# u-cont.net
KiCad netlist of a schematic drawn in Altium Designer
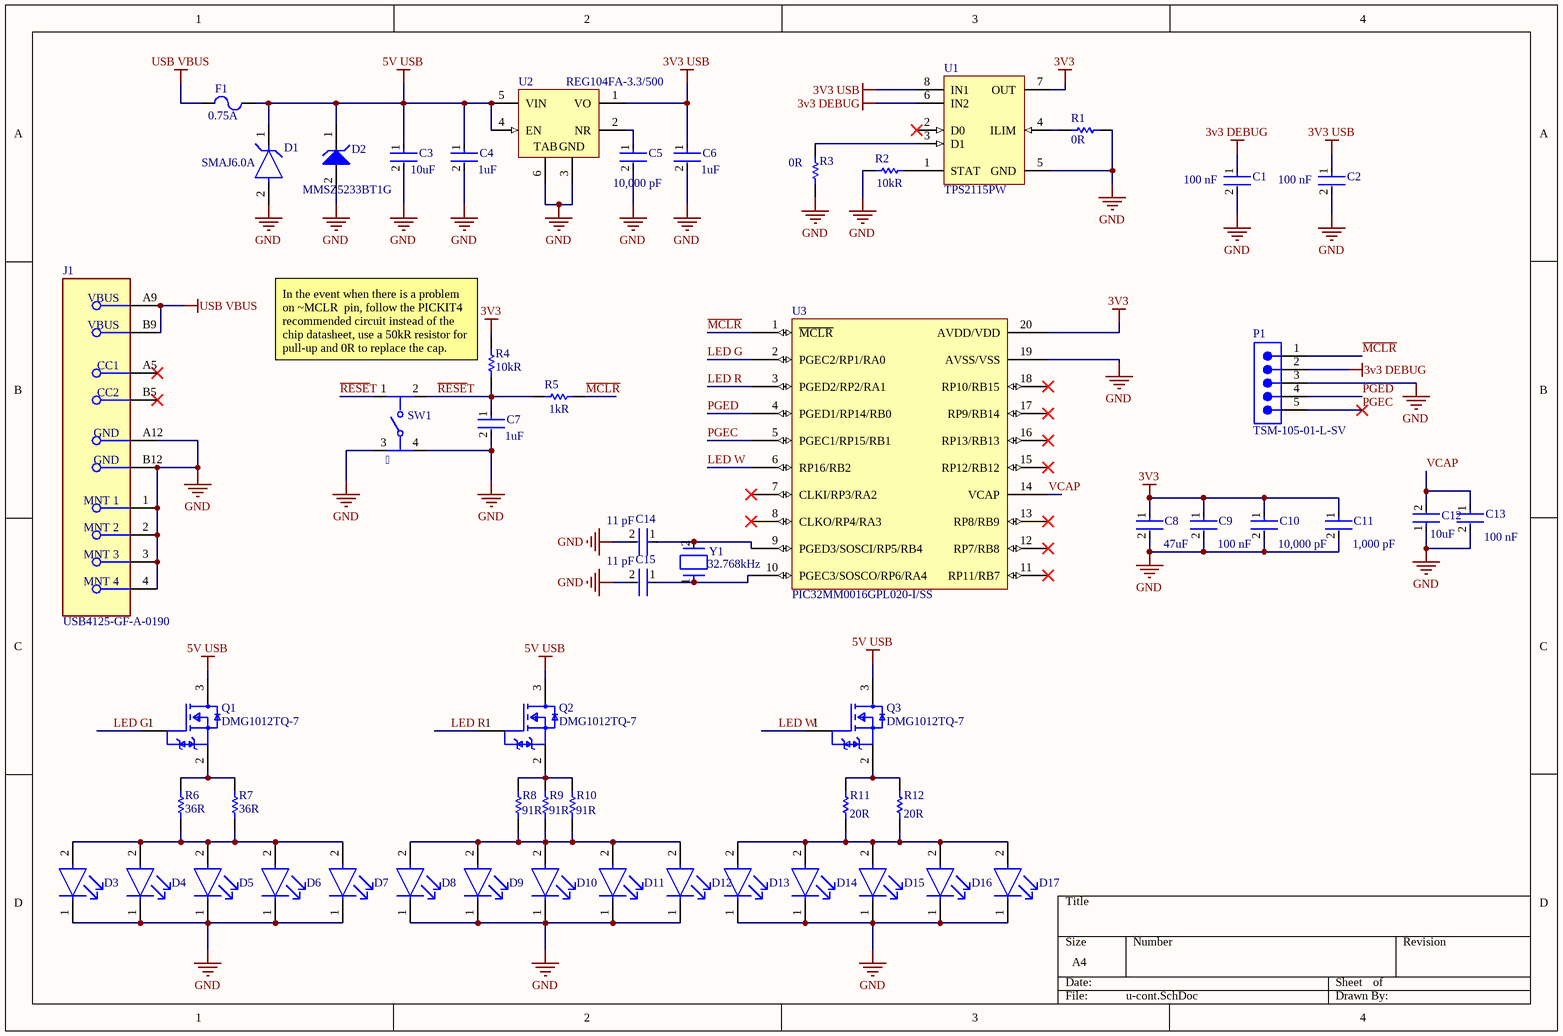
[diagram p0: u-cont.SchDoc]

(export (version "E")
  (design (tool "Eeschema 10.0.6"))
  (components
    (comp (ref "C1")
      (value "CC0805KRX7R8BB104")
      (footprint "FP-CC0805-0_85-MFG")
      (description "CAP CER 0.1UF 25V X7R 0805")
      (fields
        (field (name "TOLERANCE") "0.1")
        (field (name "MANUFACTURER") "Yageo")
        (field (name "CAPACITANCE") "100 nF")
      )
      (libsource (lib "Altium Content Vault") (part "11868f565c42a9108669ba33697ecf6"))
    )
    (comp (ref "C2")
      (value "CC0805KRX7R8BB104")
      (footprint "FP-CC0805-0_85-MFG")
      (description "CAP CER 0.1UF 25V X7R 0805")
      (fields
        (field (name "TOLERANCE") "0.1")
        (field (name "MANUFACTURER") "Yageo")
        (field (name "CAPACITANCE") "100 nF")
      )
      (libsource (lib "Altium Content Vault") (part "11868f565c42a9108669ba33697ecf6"))
    )
    (comp (ref "C3")
      (value "GRM21BR61E106KA73L")
      (footprint "FP-GRM21B-0_15-IPC_C")
      (description "Chip Multilayer Ceramic Capacitors for General Purpose, 0805, 10uF, X5R, 15%, 10%, 25V")
      (fields
        (field (name "VOLTAGE") "25V")
        (field (name "CAPACITANCE") "10uF")
        (field (name "TOLERANCE") "10%")
      )
      (libsource (lib "Altium Content Vault") (part "b4654b650e69147ec39a6b967a45e02"))
    )
    (comp (ref "C4")
      (value "C2012X5R1E105K125AA")
      (footprint "FP-C2012-125-0_2-IPC_A")
      (description "Multilayer Ceramic Capacitors 1μF ±10% 25V X5R SMD 0805")
      (fields
        (field (name "VOLTAGE") "25V")
        (field (name "CAPACITANCE") "1uF")
        (field (name "TOLERANCE") "10%")
      )
      (libsource (lib "Altium Content Vault") (part "b4654b650e69147ec39a6b967a45e02"))
    )
    (comp (ref "C5")
      (value "C0805C103J5RACTU")
      (footprint "FP-C0805C-DN-MFG")
      (description "CAP CER 10000PF 50V X7R 0805")
      (fields
        (field (name "MANUFACTURER") "KEMET")
        (field (name "CAPACITANCE") "10,000 pF")
        (field (name "OCTOPART") "https://octopart.com/c0805c103j5ractu-kemet-133473")
      )
      (libsource (lib "Altium Content Vault") (part "b4654b650e69147ec39a6b967a45e02"))
    )
    (comp (ref "C6")
      (value "C2012X5R1E105K125AA")
      (footprint "FP-C2012-125-0_2-IPC_A")
      (description "Multilayer Ceramic Capacitors 1μF ±10% 25V X5R SMD 0805")
      (fields
        (field (name "VOLTAGE") "25V")
        (field (name "CAPACITANCE") "1uF")
        (field (name "TOLERANCE") "10%")
      )
      (libsource (lib "Altium Content Vault") (part "b4654b650e69147ec39a6b967a45e02"))
    )
    (comp (ref "C7")
      (value "C2012X5R1E105K125AA")
      (footprint "FP-C2012-125-0_2-IPC_A")
      (description "Multilayer Ceramic Capacitors 1μF ±10% 25V X5R SMD 0805")
      (fields
        (field (name "VOLTAGE") "25V")
        (field (name "CAPACITANCE") "1uF")
        (field (name "TOLERANCE") "10%")
      )
      (libsource (lib "Altium Content Vault") (part "b4654b650e69147ec39a6b967a45e02"))
    )
    (comp (ref "C8")
      (value "C0805C476M9PACTU")
      (footprint "FP-C0805C476M9PACTU-MFG")
      (description "CAP CER 47UF 6.3V X5R 0805")
      (fields
        (field (name "VOLTAGE") "6.3V")
        (field (name "TOLERANCE") "20%")
        (field (name "CAPACITANCE") "47uF")
      )
      (libsource (lib "Altium Content Vault") (part "11868f565c42a9108669ba33697ecf6"))
    )
    (comp (ref "C9")
      (value "CC0805KRX7R8BB104")
      (footprint "FP-CC0805-0_85-MFG")
      (description "CAP CER 0.1UF 25V X7R 0805")
      (fields
        (field (name "TOLERANCE") "0.1")
        (field (name "MANUFACTURER") "Yageo")
        (field (name "CAPACITANCE") "100 nF")
      )
      (libsource (lib "Altium Content Vault") (part "11868f565c42a9108669ba33697ecf6"))
    )
    (comp (ref "C10")
      (value "C0805C103J5RACTU")
      (footprint "FP-C0805C-DN-MFG")
      (description "CAP CER 10000PF 50V X7R 0805")
      (fields
        (field (name "MANUFACTURER") "KEMET")
        (field (name "CAPACITANCE") "10,000 pF")
        (field (name "OCTOPART") "https://octopart.com/c0805c103j5ractu-kemet-133473")
      )
      (libsource (lib "Altium Content Vault") (part "b4654b650e69147ec39a6b967a45e02"))
    )
    (comp (ref "C11")
      (value "C0805C102K5RACTU")
      (footprint "FP-C0805C-DN-MFG")
      (description "CAP CER 1000PF 50V X7R 0805")
      (fields
        (field (name "CAPACITANCE") "1,000 pF")
        (field (name "OCTOPART") "https://octopart.com/c0805c102k5ractu-kemet-93010")
        (field (name "TOLERANCE") "0.1")
      )
      (libsource (lib "Altium Content Vault") (part "b4654b650e69147ec39a6b967a45e02"))
    )
    (comp (ref "C12")
      (value "C0805C106K8PACTU")
      (footprint "FP-C0805C-DG-MFG")
      (description "CAP CER 10UF 10V X5R 0805")
      (fields
        (field (name "TOLERANCE") "10%")
        (field (name "MANUFACTURER") "Kemet")
        (field (name "CAPACITANCE") "10uF")
      )
      (libsource (lib "Altium Content Vault") (part "11868f565c42a9108669ba33697ecf6"))
    )
    (comp (ref "C13")
      (value "CC0805KRX7R8BB104")
      (footprint "FP-CC0805-0_85-MFG")
      (description "CAP CER 0.1UF 25V X7R 0805")
      (fields
        (field (name "TOLERANCE") "0.1")
        (field (name "MANUFACTURER") "Yageo")
        (field (name "CAPACITANCE") "100 nF")
      )
      (libsource (lib "Altium Content Vault") (part "11868f565c42a9108669ba33697ecf6"))
    )
    (comp (ref "C14")
      (value "11 pF")
      (footprint "FP-C0805C-DN-MFG")
      (description "CAP CER 11PF 50V 5% NP0 0805")
      (fields (field (name "TOLERANCE") "0.05") (field (name "MANUFACTURER PART NUMBER") "C0805C110J5GACTU"))
      (libsource (lib "Altium Content Vault") (part "b4654b650e69147ec39a6b967a45e02"))
    )
    (comp (ref "C15")
      (value "11 pF")
      (footprint "FP-C0805C-DN-MFG")
      (description "CAP CER 11PF 50V 5% NP0 0805")
      (fields (field (name "TOLERANCE") "0.05") (field (name "MANUFACTURER PART NUMBER") "C0805C110J5GACTU"))
      (libsource (lib "Altium Content Vault") (part "b4654b650e69147ec39a6b967a45e02"))
    )
    (comp (ref "D1")
      (value "SMAJ6.0A")
      (footprint "FP-SMAJ-MFG")
      (description "TVS DIODE 6V 10.3V DO214AC")
      (fields
        (field (name "OCTOPART") "https://octopart.com/smaj6.0a-littelfuse-350212")
        (field (name "MANUFACTURER") "Littelfuse")
      )
      (libsource (lib "Altium Content Vault") (part "f813f71cba58e380607f5dd3caf9714"))
    )
    (comp (ref "D2")
      (value "MMSZ5233BT1G")
      (footprint "ONSC-SOD-123-2-425-04_V")
      (description "Zener Voltage Regulator, 500 mW, 2-Pin SOD-123, Pb-Free, Tape and Reel")
      (fields (field (name "MANUFACTURER") "On Semiconductor"))
      (libsource (lib "Altium Content Vault") (part "ONSC-K1A2-2"))
    )
    (comp (ref "D3")
      (value "150060GS75000")
      (footprint "FP-150060GS75000-MFG")
      (description "Led, Green, 520 Nm, 3.2 V, 30 Ma, 430 Mcd Rohs Compliant: Yes")
      (libsource (lib "Open Robotics Drivetrain ELEC") (part "8706943c75ba83719d021d2fdc84c58"))
    )
    (comp (ref "D4")
      (value "150060GS75000")
      (footprint "FP-150060GS75000-MFG")
      (description "Led, Green, 520 Nm, 3.2 V, 30 Ma, 430 Mcd Rohs Compliant: Yes")
      (libsource (lib "Open Robotics Drivetrain ELEC") (part "8706943c75ba83719d021d2fdc84c58"))
    )
    (comp (ref "D5")
      (value "150060GS75000")
      (footprint "FP-150060GS75000-MFG")
      (description "Led, Green, 520 Nm, 3.2 V, 30 Ma, 430 Mcd Rohs Compliant: Yes")
      (libsource (lib "Open Robotics Drivetrain ELEC") (part "8706943c75ba83719d021d2fdc84c58"))
    )
    (comp (ref "D6")
      (value "150060GS75000")
      (footprint "FP-150060GS75000-MFG")
      (description "Led, Green, 520 Nm, 3.2 V, 30 Ma, 430 Mcd Rohs Compliant: Yes")
      (libsource (lib "Open Robotics Drivetrain ELEC") (part "8706943c75ba83719d021d2fdc84c58"))
    )
    (comp (ref "D7")
      (value "150060GS75000")
      (footprint "FP-150060GS75000-MFG")
      (description "Led, Green, 520 Nm, 3.2 V, 30 Ma, 430 Mcd Rohs Compliant: Yes")
      (libsource (lib "Open Robotics Drivetrain ELEC") (part "8706943c75ba83719d021d2fdc84c58"))
    )
    (comp (ref "D8")
      (value "150060GS75000")
      (footprint "FP-150060GS75000-MFG")
      (description "Led, Green, 520 Nm, 3.2 V, 30 Ma, 430 Mcd Rohs Compliant: Yes")
      (libsource (lib "Open Robotics Drivetrain ELEC") (part "8706943c75ba83719d021d2fdc84c58"))
    )
    (comp (ref "D9")
      (value "150060GS75000")
      (footprint "FP-150060GS75000-MFG")
      (description "Led, Green, 520 Nm, 3.2 V, 30 Ma, 430 Mcd Rohs Compliant: Yes")
      (libsource (lib "Open Robotics Drivetrain ELEC") (part "8706943c75ba83719d021d2fdc84c58"))
    )
    (comp (ref "D10")
      (value "150060GS75000")
      (footprint "FP-150060GS75000-MFG")
      (description "Led, Green, 520 Nm, 3.2 V, 30 Ma, 430 Mcd Rohs Compliant: Yes")
      (libsource (lib "Open Robotics Drivetrain ELEC") (part "8706943c75ba83719d021d2fdc84c58"))
    )
    (comp (ref "D11")
      (value "150060GS75000")
      (footprint "FP-150060GS75000-MFG")
      (description "Led, Green, 520 Nm, 3.2 V, 30 Ma, 430 Mcd Rohs Compliant: Yes")
      (libsource (lib "Open Robotics Drivetrain ELEC") (part "8706943c75ba83719d021d2fdc84c58"))
    )
    (comp (ref "D12")
      (value "150060GS75000")
      (footprint "FP-150060GS75000-MFG")
      (description "Led, Green, 520 Nm, 3.2 V, 30 Ma, 430 Mcd Rohs Compliant: Yes")
      (libsource (lib "Open Robotics Drivetrain ELEC") (part "8706943c75ba83719d021d2fdc84c58"))
    )
    (comp (ref "D13")
      (value "150060GS75000")
      (footprint "FP-150060GS75000-MFG")
      (description "Led, Green, 520 Nm, 3.2 V, 30 Ma, 430 Mcd Rohs Compliant: Yes")
      (libsource (lib "Open Robotics Drivetrain ELEC") (part "8706943c75ba83719d021d2fdc84c58"))
    )
    (comp (ref "D14")
      (value "150060GS75000")
      (footprint "FP-150060GS75000-MFG")
      (description "Led, Green, 520 Nm, 3.2 V, 30 Ma, 430 Mcd Rohs Compliant: Yes")
      (libsource (lib "Open Robotics Drivetrain ELEC") (part "8706943c75ba83719d021d2fdc84c58"))
    )
    (comp (ref "D15")
      (value "150060GS75000")
      (footprint "FP-150060GS75000-MFG")
      (description "Led, Green, 520 Nm, 3.2 V, 30 Ma, 430 Mcd Rohs Compliant: Yes")
      (libsource (lib "Open Robotics Drivetrain ELEC") (part "8706943c75ba83719d021d2fdc84c58"))
    )
    (comp (ref "D16")
      (value "150060GS75000")
      (footprint "FP-150060GS75000-MFG")
      (description "Led, Green, 520 Nm, 3.2 V, 30 Ma, 430 Mcd Rohs Compliant: Yes")
      (libsource (lib "Open Robotics Drivetrain ELEC") (part "8706943c75ba83719d021d2fdc84c58"))
    )
    (comp (ref "D17")
      (value "150060GS75000")
      (footprint "FP-150060GS75000-MFG")
      (description "Led, Green, 520 Nm, 3.2 V, 30 Ma, 430 Mcd Rohs Compliant: Yes")
      (libsource (lib "Open Robotics Drivetrain ELEC") (part "8706943c75ba83719d021d2fdc84c58"))
    )
    (comp (ref "F1")
      (value "1812L075/24DR")
      (footprint "LFUS-1812L07524DR_V")
      (description "Poly-Fuse(R) Resettable PTC, 24 V, 100 A, -40 to 85 degC, 2-Pin SMD, RoHS, Tape and Reel")
      (fields (field (name "MANUFACTURER") "Littelfuse") (field (name "HOLD CURRENT") "0.75A"))
      (libsource (lib "Altium Content Vault") (part "FUSE-2"))
    )
    (comp (ref "J1")
      (value "USB4125-GF-A-0190")
      (footprint "FP-USB4125-GF-A-0190-MFG")
      (description "CONN RCPT TYPE C 6P SMD RA")
      (libsource (lib "Altium Content Vault") (part "a055484d46e58b234844902c9fd883a"))
    )
    (comp (ref "P1")
      (value "TSM-105-01-L-SV")
      (footprint "SMTC-TSM-105-01-X-SV")
      (description "0.025\" SQ Post Header, Surface Mount, Vertical, -55 to 125 degC, 2.54 mm Pitch, 5-Pin, Male, RoHS")
      (fields (field (name "MANUFACTURER") "Samtec"))
      (libsource (lib "Altium Content Vault") (part "SMTC-TSM-105-01-X-SV"))
    )
    (comp (ref "Q1")
      (value "DMG1012TQ-7")
      (footprint "FP-SOT523-MFG")
      (description "MOSFET NCH 20V 630MA SOT523")
      (fields
        (field (name "OCTOPART") "https://octopart.com/dmg1012tq-7-diodes+inc.-74468997")
        (field (name "MANUFACTURER") "Diodes Inc.")
      )
      (libsource (lib "Altium Content Vault") (part "46b141b2f085c93750ed035ed02516a"))
    )
    (comp (ref "Q2")
      (value "DMG1012TQ-7")
      (footprint "FP-SOT523-MFG")
      (description "MOSFET NCH 20V 630MA SOT523")
      (fields
        (field (name "OCTOPART") "https://octopart.com/dmg1012tq-7-diodes+inc.-74468997")
        (field (name "MANUFACTURER") "Diodes Inc.")
      )
      (libsource (lib "Altium Content Vault") (part "46b141b2f085c93750ed035ed02516a"))
    )
    (comp (ref "Q3")
      (value "DMG1012TQ-7")
      (footprint "FP-SOT523-MFG")
      (description "MOSFET NCH 20V 630MA SOT523")
      (fields
        (field (name "OCTOPART") "https://octopart.com/dmg1012tq-7-diodes+inc.-74468997")
        (field (name "MANUFACTURER") "Diodes Inc.")
      )
      (libsource (lib "Altium Content Vault") (part "46b141b2f085c93750ed035ed02516a"))
    )
    (comp (ref "R1")
      (value "RC0805JR-070RL")
      (footprint "RESC2013X60X35ML10T20")
      (fields
        (field (name "RESISTANCE") "0R")
        (field (name "TOLERANCE") "5%")
        (field (name "MANUFACTURER") "Yageo")
      )
      (libsource (lib "Altium Content Vault") (part "RES-2"))
    )
    (comp (ref "R2")
      (value "RC0805FR-0710KL")
      (footprint "RESC2013X60X35NL10T20")
      (description "Chip Resistor, 10 KOhm, +/- 1%, 0.125 W, -55 to 155 degC, 0805 (2012 Metric), RoHS, Tape and Reel")
      (fields (field (name "MANUFACTURER") "Yageo") (field (name "RESISTANCE") "10kR"))
      (libsource (lib "Altium Content Vault") (part "RES-2"))
    )
    (comp (ref "R3")
      (value "RC0805JR-070RL")
      (footprint "RESC2013X60X35ML10T20")
      (fields
        (field (name "RESISTANCE") "0R")
        (field (name "TOLERANCE") "5%")
        (field (name "MANUFACTURER") "Yageo")
      )
      (libsource (lib "Altium Content Vault") (part "RES-2"))
    )
    (comp (ref "R4")
      (value "10kR")
      (footprint "RESC2013X60X35NL10T20")
      (description "Chip Resistor, 10 KOhm, +/- 1%, 0.125 W, -55 to 155 degC, 0805 (2012 Metric), RoHS, Tape and Reel")
      (fields (field (name "MANUFACTURER") "Yageo") (field (name "Comment") "RC0805FR-0710KL"))
      (libsource (lib "Altium Content Vault") (part "RES-2"))
    )
    (comp (ref "R5")
      (value "RC0805FR-071KL")
      (footprint "RESC2013X60X35ML10T20")
      (description "Chip Resistor, 1 KOhm, +/- 1%, 125 mW, -55 to 155 degC, 0805 (2012 Metric), RoHS, Tape and Reel")
      (fields
        (field (name "RESISTANCE") "1kR")
        (field (name "TOLERANCE") "1%")
        (field (name "MANUFACTURER") "Yageo")
      )
      (libsource (lib "Altium Content Vault") (part "RES-2"))
    )
    (comp (ref "R6")
      (value "36R")
      (footprint "RESC0805(2012)_L")
      (description "36R 0.125W 1% 0805 (2012 Metric)  SMD")
      (fields (field (name "POWER") "0.125 W") (field (name "TOLERANCE") "1 %"))
      (libsource (lib "Altium Content Vault") (part "RES"))
    )
    (comp (ref "R7")
      (value "36R")
      (footprint "RESC0805(2012)_L")
      (description "36R 0.125W 1% 0805 (2012 Metric)  SMD")
      (fields (field (name "POWER") "0.125 W") (field (name "TOLERANCE") "1 %"))
      (libsource (lib "Altium Content Vault") (part "RES"))
    )
    (comp (ref "R8")
      (value "ERJ-6GEYJ910V")
      (footprint "RESC2013X70X40NL20T20")
      (fields (field (name "MANUFACTURER") "Panasonic") (field (name "PARAMETER 1") "91R"))
      (libsource (lib "Altium Content Vault") (part "RES"))
    )
    (comp (ref "R9")
      (value "ERJ-6GEYJ910V")
      (footprint "RESC2013X70X40NL20T20")
      (fields (field (name "MANUFACTURER") "Panasonic") (field (name "PARAMETER 1") "91R"))
      (libsource (lib "Altium Content Vault") (part "RES"))
    )
    (comp (ref "R10")
      (value "ERJ-6GEYJ910V")
      (footprint "RESC2013X70X40NL20T20")
      (fields (field (name "MANUFACTURER") "Panasonic") (field (name "PARAMETER 1") "91R"))
      (libsource (lib "Altium Content Vault") (part "RES"))
    )
    (comp (ref "R11")
      (value "ERJ-6ENF20R0V")
      (footprint "RESC2013X70X40ML20T20")
      (fields (field (name "MANUFACTURER") "Panasonic") (field (name "PARAMETER 1") "20R"))
      (libsource (lib "Altium Content Vault") (part "RES"))
    )
    (comp (ref "R12")
      (value "ERJ-6ENF20R0V")
      (footprint "RESC2013X70X40ML20T20")
      (fields (field (name "MANUFACTURER") "Panasonic") (field (name "PARAMETER 1") "20R"))
      (libsource (lib "Altium Content Vault") (part "RES"))
    )
    (comp (ref "SW1")
      (value "")
      (footprint "FP-PTS645SM43SMTR92LFS-MFG")
      (description "SWITCH TACTILE SPST-NO 0.05A 12V")
      (libsource (lib "Altium Content Vault") (part "1adf0dd01260c80cf25a44bfd6b99ba"))
    )
    (comp (ref "U1")
      (value "TPS2115PW")
      (footprint "PW0008A_N")
      (fields (field (name "MANUFACTURER") "Texas Instruments"))
      (libsource (lib "Altium Content Vault") (part "TI-TPS2115PW8"))
    )
    (comp (ref "U2")
      (value "REG104FA-3.3/500")
      (footprint "KTT0005A_N")
      (fields (field (name "MANUFACTURER") "Texas Instruments"))
      (libsource (lib "Altium Content Vault") (part "TI-REG10X-XXKTT5"))
    )
    (comp (ref "U3")
      (value "PIC32MM0016GPL020-I/SS")
      (footprint "SOP65P780X200-20N")
      (libsource (lib "ucont") (part "PIC32MM0016GPL020-I/SS"))
    )
    (comp (ref "Y1")
      (value "ABS06-32.768KHZ-1-T")
      (footprint "FP-ABS06-MFG")
      (description "CRYSTAL 32.7680KHZ 12.5PF SMD")
      (fields (field (name "FREQUENCY") "32.768kHz") (field (name "TOLERANCE") "10ppm"))
      (libsource (lib "Altium Content Vault") (part "c23a69dc6c9e2f18f2079038eb95dd1"))
    )
  )
  (nets
    (net (code "1") (name "/LED G") (class "Default")
      (node (ref "Q1") (pin "1") (pinfunction "G_1") (pintype "passive"))
      (node (ref "U3") (pin "2") (pinfunction "PGEC2/RP1/RA0_2") (pintype "bidirectional"))
    )
    (net (code "2") (name "/LED R") (class "Default")
      (node (ref "Q2") (pin "1") (pinfunction "G_1") (pintype "passive"))
      (node (ref "U3") (pin "3") (pinfunction "PGED2/RP2/RA1_3") (pintype "bidirectional"))
    )
    (net (code "3") (name "/LED W") (class "Default")
      (node (ref "Q3") (pin "1") (pinfunction "G_1") (pintype "passive"))
      (node (ref "U3") (pin "6") (pinfunction "RP16/RB2_6") (pintype "bidirectional"))
    )
    (net (code "4") (name "/PGEC") (class "Default")
      (node (ref "P1") (pin "5") (pinfunction "5_5") (pintype "passive"))
      (node (ref "U3") (pin "5") (pinfunction "PGEC1/RP15/RB1_5") (pintype "bidirectional"))
    )
    (net (code "5") (name "/PGED") (class "Default")
      (node (ref "P1") (pin "4") (pinfunction "4_4") (pintype "passive"))
      (node (ref "U3") (pin "4") (pinfunction "PGED1/RP14/RB0_4") (pintype "bidirectional"))
    )
    (net (code "6") (name "/VCAP") (class "Default")
      (node (ref "C12") (pin "2") (pinfunction "2_2") (pintype "passive"))
      (node (ref "C13") (pin "1") (pinfunction "1_1") (pintype "passive"))
      (node (ref "U3") (pin "14") (pinfunction "VCAP_14") (pintype "power_in"))
    )
    (net (code "7") (name "/~{MCLR}") (class "Default")
      (node (ref "P1") (pin "1") (pinfunction "1_1") (pintype "passive"))
      (node (ref "R5") (pin "2") (pinfunction "2_2") (pintype "passive"))
      (node (ref "U3") (pin "1") (pinfunction "~{MCLR}_1") (pintype "bidirectional"))
    )
    (net (code "8") (name "/~{RESE}T") (class "Default")
      (node (ref "C7") (pin "1") (pinfunction "1_1") (pintype "passive"))
      (node (ref "R4") (pin "2") (pinfunction "2_2") (pintype "passive"))
      (node (ref "R5") (pin "1") (pinfunction "1_1") (pintype "passive"))
      (node (ref "SW1") (pin "1") (pinfunction "1_1") (pintype "passive"))
      (node (ref "SW1") (pin "2") (pinfunction "2_2") (pintype "passive"))
    )
    (net (code "9") (name "3V3") (class "Default")
      (node (ref "C10") (pin "1") (pinfunction "1_1") (pintype "passive"))
      (node (ref "C11") (pin "1") (pinfunction "1_1") (pintype "passive"))
      (node (ref "C8") (pin "1") (pinfunction "1_1") (pintype "passive"))
      (node (ref "C9") (pin "1") (pinfunction "1_1") (pintype "passive"))
      (node (ref "R4") (pin "1") (pinfunction "1_1") (pintype "passive"))
      (node (ref "U1") (pin "7") (pinfunction "OUT_7") (pintype "power_in"))
      (node (ref "U3") (pin "20") (pinfunction "AVDD/VDD_20") (pintype "power_in"))
    )
    (net (code "10") (name "3V3 USB") (class "Default")
      (node (ref "C2") (pin "1") (pinfunction "1_1") (pintype "passive"))
      (node (ref "C6") (pin "1") (pinfunction "1_1") (pintype "passive"))
      (node (ref "U1") (pin "8") (pinfunction "IN1_8") (pintype "power_in"))
      (node (ref "U2") (pin "1") (pinfunction "VO_1") (pintype "power_in"))
    )
    (net (code "11") (name "3v3 DEBUG") (class "Default")
      (node (ref "C1") (pin "1") (pinfunction "1_1") (pintype "passive"))
      (node (ref "P1") (pin "2") (pinfunction "2_2") (pintype "passive"))
      (node (ref "U1") (pin "6") (pinfunction "IN2_6") (pintype "power_in"))
    )
    (net (code "12") (name "5V USB") (class "Default")
      (node (ref "C3") (pin "1") (pinfunction "1_1") (pintype "passive"))
      (node (ref "C4") (pin "1") (pinfunction "1_1") (pintype "passive"))
      (node (ref "D1") (pin "1") (pinfunction "C_1") (pintype "passive"))
      (node (ref "D2") (pin "1") (pinfunction "K_1") (pintype "passive"))
      (node (ref "F1") (pin "2") (pinfunction "2_2") (pintype "passive"))
      (node (ref "Q1") (pin "3") (pinfunction "D_3") (pintype "passive"))
      (node (ref "Q2") (pin "3") (pinfunction "D_3") (pintype "passive"))
      (node (ref "Q3") (pin "3") (pinfunction "D_3") (pintype "passive"))
      (node (ref "U2") (pin "4") (pinfunction "EN_4") (pintype "input"))
      (node (ref "U2") (pin "5") (pinfunction "VIN_5") (pintype "power_in"))
    )
    (net (code "13") (name "GND") (class "Default")
      (node (ref "C1") (pin "2") (pinfunction "2_2") (pintype "passive"))
      (node (ref "C10") (pin "2") (pinfunction "2_2") (pintype "passive"))
      (node (ref "C11") (pin "2") (pinfunction "2_2") (pintype "passive"))
      (node (ref "C12") (pin "1") (pinfunction "1_1") (pintype "passive"))
      (node (ref "C13") (pin "2") (pinfunction "2_2") (pintype "passive"))
      (node (ref "C14") (pin "2") (pinfunction "2_2") (pintype "passive"))
      (node (ref "C15") (pin "2") (pinfunction "2_2") (pintype "passive"))
      (node (ref "C2") (pin "2") (pinfunction "2_2") (pintype "passive"))
      (node (ref "C3") (pin "2") (pinfunction "2_2") (pintype "passive"))
      (node (ref "C4") (pin "2") (pinfunction "2_2") (pintype "passive"))
      (node (ref "C5") (pin "2") (pinfunction "2_2") (pintype "passive"))
      (node (ref "C6") (pin "2") (pinfunction "2_2") (pintype "passive"))
      (node (ref "C7") (pin "2") (pinfunction "2_2") (pintype "passive"))
      (node (ref "C8") (pin "2") (pinfunction "2_2") (pintype "passive"))
      (node (ref "C9") (pin "2") (pinfunction "2_2") (pintype "passive"))
      (node (ref "D1") (pin "2") (pinfunction "A_2") (pintype "passive"))
      (node (ref "D10") (pin "1") (pinfunction "C_1") (pintype "passive"))
      (node (ref "D11") (pin "1") (pinfunction "C_1") (pintype "passive"))
      (node (ref "D12") (pin "1") (pinfunction "C_1") (pintype "passive"))
      (node (ref "D13") (pin "1") (pinfunction "C_1") (pintype "passive"))
      (node (ref "D14") (pin "1") (pinfunction "C_1") (pintype "passive"))
      (node (ref "D15") (pin "1") (pinfunction "C_1") (pintype "passive"))
      (node (ref "D16") (pin "1") (pinfunction "C_1") (pintype "passive"))
      (node (ref "D17") (pin "1") (pinfunction "C_1") (pintype "passive"))
      (node (ref "D2") (pin "2") (pinfunction "A_2") (pintype "passive"))
      (node (ref "D3") (pin "1") (pinfunction "C_1") (pintype "passive"))
      (node (ref "D4") (pin "1") (pinfunction "C_1") (pintype "passive"))
      (node (ref "D5") (pin "1") (pinfunction "C_1") (pintype "passive"))
      (node (ref "D6") (pin "1") (pinfunction "C_1") (pintype "passive"))
      (node (ref "D7") (pin "1") (pinfunction "C_1") (pintype "passive"))
      (node (ref "D8") (pin "1") (pinfunction "C_1") (pintype "passive"))
      (node (ref "D9") (pin "1") (pinfunction "C_1") (pintype "passive"))
      (node (ref "J1") (pin "1") (pinfunction "MNT_1_1") (pintype "passive"))
      (node (ref "J1") (pin "2") (pinfunction "MNT_2_2") (pintype "passive"))
      (node (ref "J1") (pin "3") (pinfunction "MNT_3_3") (pintype "passive"))
      (node (ref "J1") (pin "4") (pinfunction "MNT_4_4") (pintype "passive"))
      (node (ref "J1") (pin "A12") (pinfunction "GND_A12") (pintype "passive"))
      (node (ref "J1") (pin "B12") (pinfunction "GND_B12") (pintype "passive"))
      (node (ref "P1") (pin "3") (pinfunction "3_3") (pintype "passive"))
      (node (ref "R1") (pin "1") (pinfunction "1_1") (pintype "passive"))
      (node (ref "R2") (pin "1") (pinfunction "1_1") (pintype "passive"))
      (node (ref "R3") (pin "1") (pinfunction "1_1") (pintype "passive"))
      (node (ref "SW1") (pin "3") (pinfunction "3_3") (pintype "passive"))
      (node (ref "SW1") (pin "4") (pinfunction "4_4") (pintype "passive"))
      (node (ref "U1") (pin "5") (pinfunction "GND_5") (pintype "power_in"))
      (node (ref "U2") (pin "3") (pinfunction "GND_3") (pintype "power_in"))
      (node (ref "U2") (pin "6") (pinfunction "TAB_6") (pintype "power_in"))
      (node (ref "U3") (pin "19") (pinfunction "AVSS/VSS_19") (pintype "power_in"))
    )
    (net (code "14") (name "Net-(D3-A)") (class "Default")
      (node (ref "D3") (pin "2") (pinfunction "A_2") (pintype "passive"))
      (node (ref "D4") (pin "2") (pinfunction "A_2") (pintype "passive"))
      (node (ref "D5") (pin "2") (pinfunction "A_2") (pintype "passive"))
      (node (ref "D6") (pin "2") (pinfunction "A_2") (pintype "passive"))
      (node (ref "D7") (pin "2") (pinfunction "A_2") (pintype "passive"))
      (node (ref "R6") (pin "1") (pinfunction "1_1") (pintype "passive"))
      (node (ref "R7") (pin "1") (pinfunction "1_1") (pintype "passive"))
    )
    (net (code "15") (name "Net-(D10-A)") (class "Default")
      (node (ref "D10") (pin "2") (pinfunction "A_2") (pintype "passive"))
      (node (ref "D11") (pin "2") (pinfunction "A_2") (pintype "passive"))
      (node (ref "D12") (pin "2") (pinfunction "A_2") (pintype "passive"))
      (node (ref "D8") (pin "2") (pinfunction "A_2") (pintype "passive"))
      (node (ref "D9") (pin "2") (pinfunction "A_2") (pintype "passive"))
      (node (ref "R10") (pin "1") (pinfunction "1_1") (pintype "passive"))
      (node (ref "R8") (pin "1") (pinfunction "1_1") (pintype "passive"))
      (node (ref "R9") (pin "1") (pinfunction "1_1") (pintype "passive"))
    )
    (net (code "16") (name "Net-(D13-A)") (class "Default")
      (node (ref "D13") (pin "2") (pinfunction "A_2") (pintype "passive"))
      (node (ref "D14") (pin "2") (pinfunction "A_2") (pintype "passive"))
      (node (ref "D15") (pin "2") (pinfunction "A_2") (pintype "passive"))
      (node (ref "D16") (pin "2") (pinfunction "A_2") (pintype "passive"))
      (node (ref "D17") (pin "2") (pinfunction "A_2") (pintype "passive"))
      (node (ref "R11") (pin "1") (pinfunction "1_1") (pintype "passive"))
      (node (ref "R12") (pin "1") (pinfunction "1_1") (pintype "passive"))
    )
    (net (code "17") (name "Net-(Q1-S)") (class "Default")
      (node (ref "Q1") (pin "2") (pinfunction "S_2") (pintype "passive"))
      (node (ref "R6") (pin "2") (pinfunction "2_2") (pintype "passive"))
      (node (ref "R7") (pin "2") (pinfunction "2_2") (pintype "passive"))
    )
    (net (code "18") (name "Net-(Q2-S)") (class "Default")
      (node (ref "Q2") (pin "2") (pinfunction "S_2") (pintype "passive"))
      (node (ref "R10") (pin "2") (pinfunction "2_2") (pintype "passive"))
      (node (ref "R8") (pin "2") (pinfunction "2_2") (pintype "passive"))
      (node (ref "R9") (pin "2") (pinfunction "2_2") (pintype "passive"))
    )
    (net (code "19") (name "Net-(Q3-S)") (class "Default")
      (node (ref "Q3") (pin "2") (pinfunction "S_2") (pintype "passive"))
      (node (ref "R11") (pin "2") (pinfunction "2_2") (pintype "passive"))
      (node (ref "R12") (pin "2") (pinfunction "2_2") (pintype "passive"))
    )
    (net (code "20") (name "Net-(U1-D1)") (class "Default")
      (node (ref "R3") (pin "2") (pinfunction "2_2") (pintype "passive"))
      (node (ref "U1") (pin "3") (pinfunction "D1_3") (pintype "input"))
    )
    (net (code "21") (name "Net-(U1-ILIM)") (class "Default")
      (node (ref "R1") (pin "2") (pinfunction "2_2") (pintype "passive"))
      (node (ref "U1") (pin "4") (pinfunction "ILIM_4") (pintype "input"))
    )
    (net (code "22") (name "Net-(U1-STAT)") (class "Default")
      (node (ref "R2") (pin "2") (pinfunction "2_2") (pintype "passive"))
      (node (ref "U1") (pin "1") (pinfunction "STAT_1") (pintype "tri_state"))
    )
    (net (code "23") (name "Net-(U2-NR)") (class "Default")
      (node (ref "C5") (pin "1") (pinfunction "1_1") (pintype "passive"))
      (node (ref "U2") (pin "2") (pinfunction "NR_2") (pintype "passive"))
    )
    (net (code "24") (name "Net-(U3-PGEC3{slash}SOSCO{slash}RP6{slash}RA4)") (class "Default")
      (node (ref "C15") (pin "1") (pinfunction "1_1") (pintype "passive"))
      (node (ref "U3") (pin "10") (pinfunction "PGEC3/SOSCO/RP6/RA4_10") (pintype "bidirectional"))
      (node (ref "Y1") (pin "1") (pinfunction "1_1") (pintype "passive"))
    )
    (net (code "25") (name "Net-(U3-PGED3{slash}SOSCI{slash}RP5{slash}RB4)") (class "Default")
      (node (ref "C14") (pin "1") (pinfunction "1_1") (pintype "passive"))
      (node (ref "U3") (pin "9") (pinfunction "PGED3/SOSCI/RP5/RB4_9") (pintype "bidirectional"))
      (node (ref "Y1") (pin "2") (pinfunction "2_2") (pintype "passive"))
    )
    (net (code "26") (name "USB VBUS") (class "Default")
      (node (ref "F1") (pin "1") (pinfunction "1_1") (pintype "passive"))
      (node (ref "J1") (pin "A9") (pinfunction "VBUS_A9") (pintype "passive"))
      (node (ref "J1") (pin "B9") (pinfunction "VBUS_B9") (pintype "passive"))
    )
    (net (code "27") (name "unconnected-(J1-CC1-PadA5)") (class "Default")
      (node (ref "J1") (pin "A5") (pinfunction "CC1_A5") (pintype "passive+no_connect"))
    )
    (net (code "28") (name "unconnected-(J1-CC2-PadB5)") (class "Default")
      (node (ref "J1") (pin "B5") (pinfunction "CC2_B5") (pintype "passive+no_connect"))
    )
    (net (code "29") (name "unconnected-(U1-D0-Pad2)") (class "Default")
      (node (ref "U1") (pin "2") (pinfunction "D0_2") (pintype "input+no_connect"))
    )
    (net (code "30") (name "unconnected-(U3-CLKI{slash}RP3{slash}RA2-Pad7)") (class "Default")
      (node (ref "U3") (pin "7") (pinfunction "CLKI/RP3/RA2_7") (pintype "bidirectional+no_connect"))
    )
    (net (code "31") (name "unconnected-(U3-CLKO{slash}RP4{slash}RA3-Pad8)") (class "Default")
      (node (ref "U3") (pin "8") (pinfunction "CLKO/RP4/RA3_8") (pintype "bidirectional+no_connect"))
    )
    (net (code "32") (name "unconnected-(U3-RP7{slash}RB8-Pad12)") (class "Default")
      (node (ref "U3") (pin "12") (pinfunction "RP7/RB8_12") (pintype "bidirectional+no_connect"))
    )
    (net (code "33") (name "unconnected-(U3-RP8{slash}RB9-Pad13)") (class "Default")
      (node (ref "U3") (pin "13") (pinfunction "RP8/RB9_13") (pintype "bidirectional+no_connect"))
    )
    (net (code "34") (name "unconnected-(U3-RP9{slash}RB14-Pad17)") (class "Default")
      (node (ref "U3") (pin "17") (pinfunction "RP9/RB14_17") (pintype "bidirectional+no_connect"))
    )
    (net (code "35") (name "unconnected-(U3-RP10{slash}RB15-Pad18)") (class "Default")
      (node (ref "U3") (pin "18") (pinfunction "RP10/RB15_18") (pintype "bidirectional+no_connect"))
    )
    (net (code "36") (name "unconnected-(U3-RP11{slash}RB7-Pad11)") (class "Default")
      (node (ref "U3") (pin "11") (pinfunction "RP11/RB7_11") (pintype "bidirectional+no_connect"))
    )
    (net (code "37") (name "unconnected-(U3-RP12{slash}RB12-Pad15)") (class "Default")
      (node (ref "U3") (pin "15") (pinfunction "RP12/RB12_15") (pintype "bidirectional+no_connect"))
    )
    (net (code "38") (name "unconnected-(U3-RP13{slash}RB13-Pad16)") (class "Default")
      (node (ref "U3") (pin "16") (pinfunction "RP13/RB13_16") (pintype "bidirectional+no_connect"))
    )
  )
)
